# hat_v1.net
KiCad netlist of a schematic drawn in EAGLE
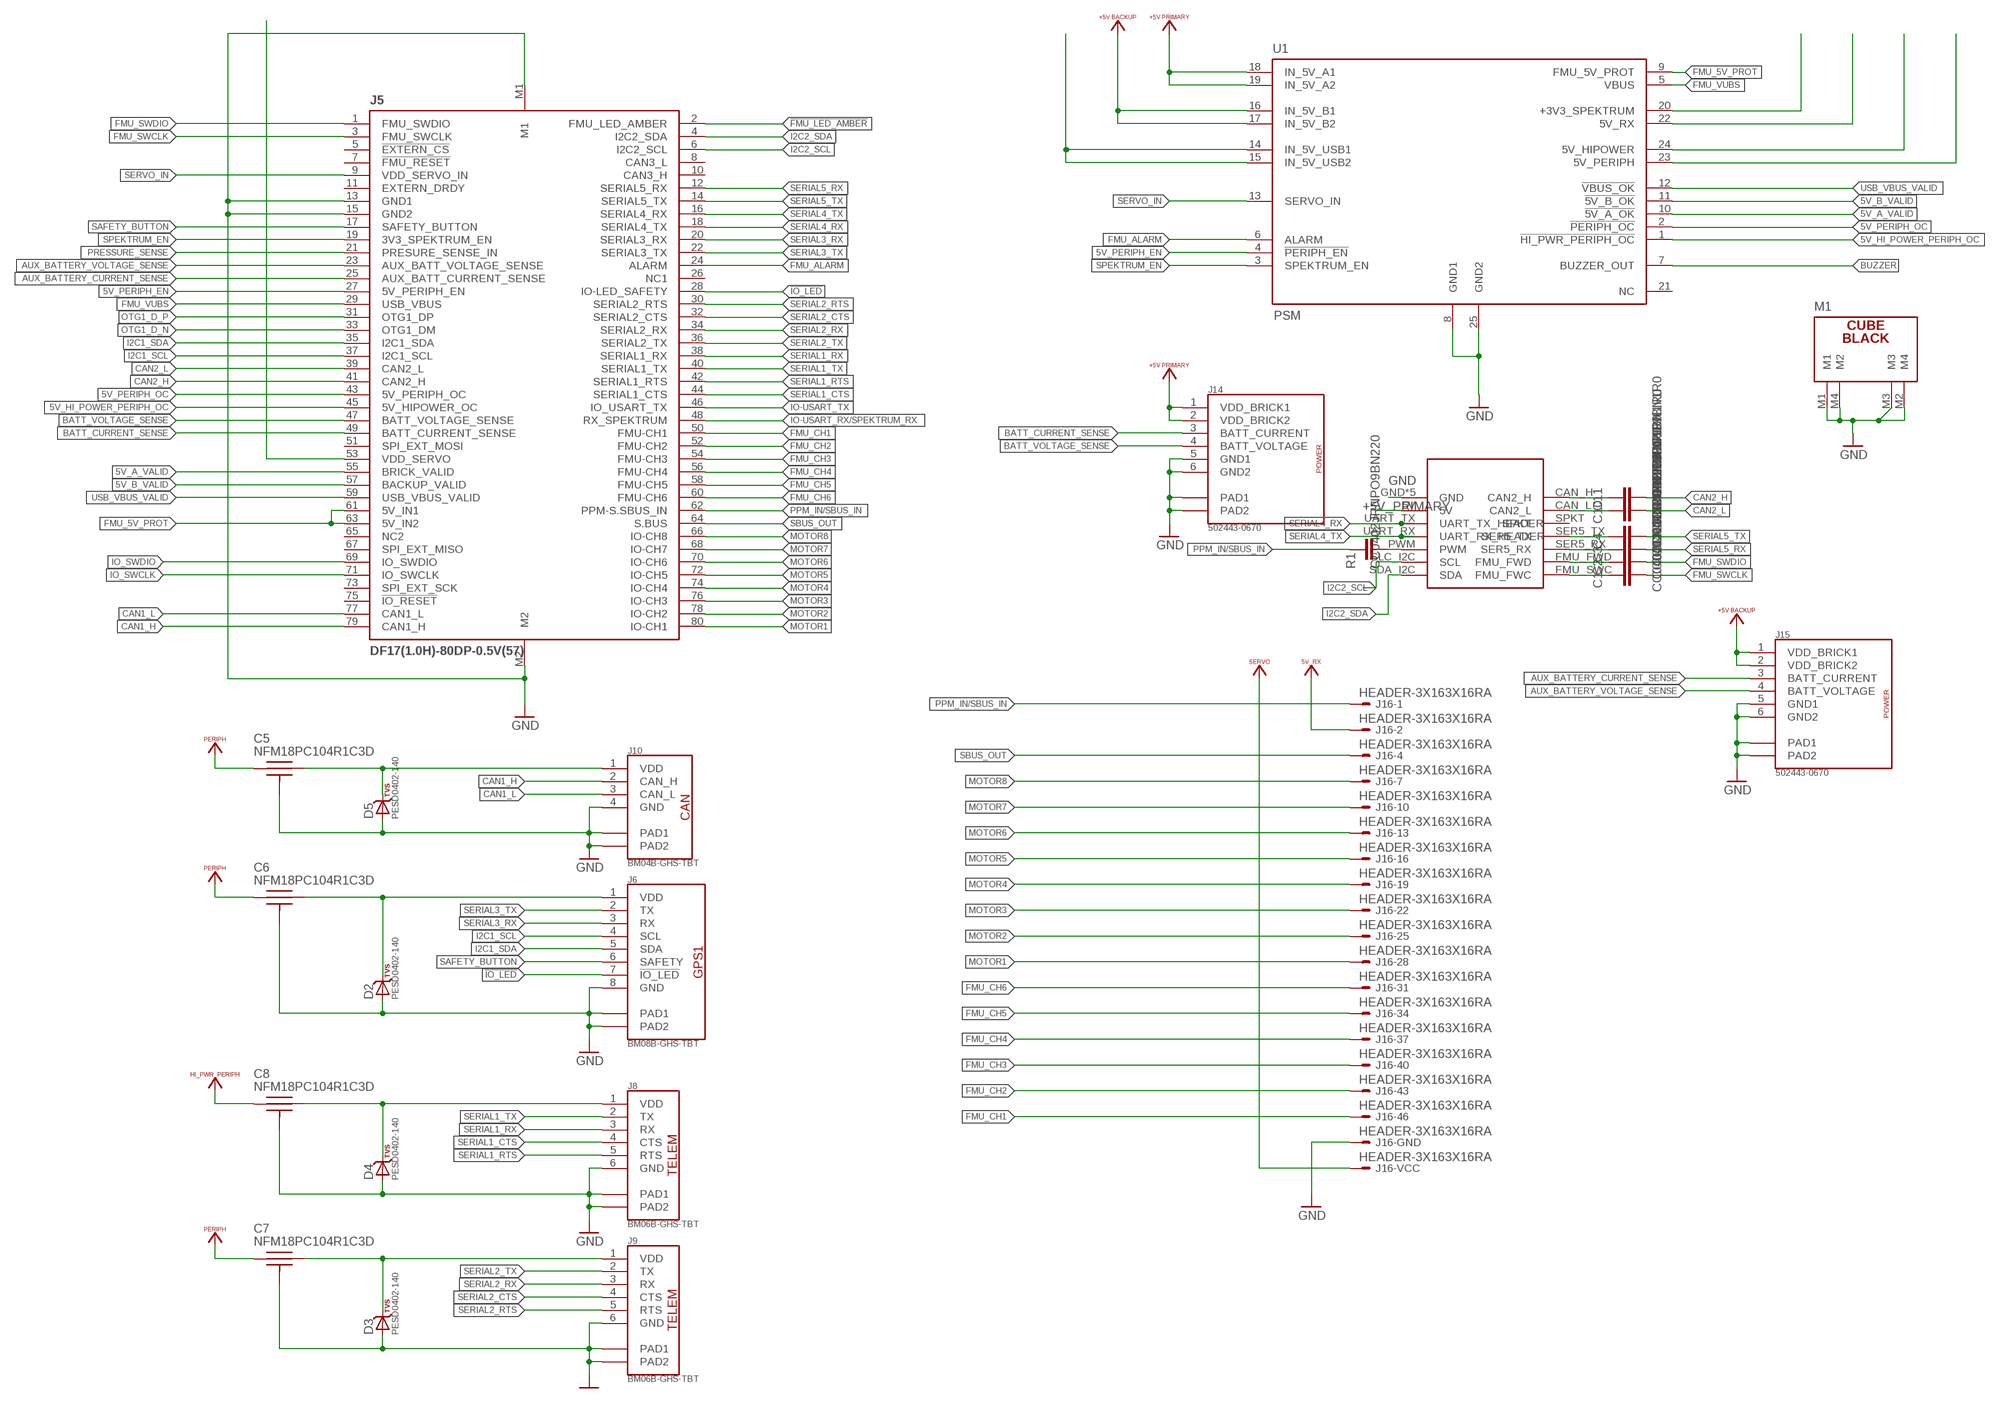
[diagram p0: schematic, sheet 1]

(export (version "E")
  (design (tool "Eeschema 10.0.6"))
  (components
    (comp (ref "C1")
      (value "CC0402CRNPO9BN1R0")
      (footprint "eagle-import:CAP_0402")
      (fields
        (field (name "DIGIKEY_PART_NUMBER") "311-2076-2-ND")
        (field (name "MANUFACTURER") "Yageo")
        (field (name "CREATED_BY") "PCBLayout.com")
      )
      (libsource (lib "eagle-import") (part "CC0402CRNPO9BN1R0"))
    )
    (comp (ref "C2")
      (value "CC0402CRNPO9BN1R0")
      (footprint "eagle-import:CAP_0402")
      (fields
        (field (name "DIGIKEY_PART_NUMBER") "311-2076-2-ND")
        (field (name "MANUFACTURER") "Yageo")
        (field (name "CREATED_BY") "PCBLayout.com")
      )
      (libsource (lib "eagle-import") (part "CC0402CRNPO9BN1R0"))
    )
    (comp (ref "C3")
      (value "CC0402CRNPO9BN1R0")
      (footprint "eagle-import:CAP_0402")
      (fields
        (field (name "DIGIKEY_PART_NUMBER") "311-2076-2-ND")
        (field (name "MANUFACTURER") "Yageo")
        (field (name "CREATED_BY") "PCBLayout.com")
      )
      (libsource (lib "eagle-import") (part "CC0402CRNPO9BN1R0"))
    )
    (comp (ref "C4")
      (value "CC0402CRNPO9BN1R0")
      (footprint "eagle-import:CAP_0402")
      (fields
        (field (name "DIGIKEY_PART_NUMBER") "311-2076-2-ND")
        (field (name "MANUFACTURER") "Yageo")
        (field (name "CREATED_BY") "PCBLayout.com")
      )
      (libsource (lib "eagle-import") (part "CC0402CRNPO9BN1R0"))
    )
    (comp (ref "C5")
      (value "NFM18PC104R1C3D")
      (footprint "eagle-import:KYOCERA-KNH16-DA")
      (libsource (lib "eagle-import") (part "NFM18PC104R1C3D"))
    )
    (comp (ref "C6")
      (value "NFM18PC104R1C3D")
      (footprint "eagle-import:KYOCERA-KNH16-DA")
      (libsource (lib "eagle-import") (part "NFM18PC104R1C3D"))
    )
    (comp (ref "C7")
      (value "NFM18PC104R1C3D")
      (footprint "eagle-import:KYOCERA-KNH16-DA")
      (libsource (lib "eagle-import") (part "NFM18PC104R1C3D"))
    )
    (comp (ref "C8")
      (value "NFM18PC104R1C3D")
      (footprint "eagle-import:KYOCERA-KNH16-DA")
      (libsource (lib "eagle-import") (part "NFM18PC104R1C3D"))
    )
    (comp (ref "C10")
      (value "CC0402CRNPO9BN1R0")
      (footprint "eagle-import:CAP_0402")
      (fields
        (field (name "DIGIKEY_PART_NUMBER") "311-2076-2-ND")
        (field (name "MANUFACTURER") "Yageo")
        (field (name "CREATED_BY") "PCBLayout.com")
      )
      (libsource (lib "eagle-import") (part "CC0402CRNPO9BN1R0"))
    )
    (comp (ref "C11")
      (value "CC0402CRNPO9BN1R0")
      (footprint "eagle-import:CAP_0402")
      (fields
        (field (name "DIGIKEY_PART_NUMBER") "311-2076-2-ND")
        (field (name "MANUFACTURER") "Yageo")
        (field (name "CREATED_BY") "PCBLayout.com")
      )
      (libsource (lib "eagle-import") (part "CC0402CRNPO9BN1R0"))
    )
    (comp (ref "D2")
      (value "PESD0402-140")
      (footprint "eagle-import:0402-TVS")
      (libsource (lib "eagle-import") (part "DIODE-TVS"))
    )
    (comp (ref "D3")
      (value "PESD0402-140")
      (footprint "eagle-import:0402-TVS")
      (libsource (lib "eagle-import") (part "DIODE-TVS"))
    )
    (comp (ref "D4")
      (value "PESD0402-140")
      (footprint "eagle-import:0402-TVS")
      (libsource (lib "eagle-import") (part "DIODE-TVS"))
    )
    (comp (ref "D5")
      (value "PESD0402-140")
      (footprint "eagle-import:0402-TVS")
      (libsource (lib "eagle-import") (part "DIODE-TVS"))
    )
    (comp (ref "J5")
      (value "DF17(1.0H)-80DP-0.5V(57)")
      (footprint "eagle-import:DF17(1.0H)-80DP-0.5V(57)")
      (libsource (lib "eagle-import") (part "DF17(1.0H)-80DP-0.5V(57)"))
    )
    (comp (ref "J6")
      (value "BM08B-GHS-TBT")
      (footprint "eagle-import:BM08B-GHS-TBT")
      (libsource (lib "eagle-import") (part "GPS1_CONNECTORBS-TBT"))
    )
    (comp (ref "J8")
      (value "BM06B-GHS-TBT")
      (footprint "eagle-import:BM06B-GHS-TBT")
      (fields (field (name "PARTNO") "BM06B-GHS-TBT(LF)(SN)"))
      (libsource (lib "eagle-import") (part "TELEM_CONNECTORBS-TBT"))
    )
    (comp (ref "J9")
      (value "BM06B-GHS-TBT")
      (footprint "eagle-import:BM06B-GHS-TBT")
      (fields (field (name "PARTNO") "BM06B-GHS-TBT(LF)(SN)"))
      (libsource (lib "eagle-import") (part "TELEM_CONNECTORBS-TBT"))
    )
    (comp (ref "J10")
      (value "BM04B-GHS-TBT")
      (footprint "eagle-import:BM04B-GHS-TBT")
      (fields (field (name "PARTNO") "BM04B-GHS-TBT(LF)(SN)"))
      (libsource (lib "eagle-import") (part "CAN_CONNECTORBS-TBT"))
    )
    (comp (ref "J14")
      (value "502443-0670")
      (footprint "eagle-import:502443-0670")
      (libsource (lib "eagle-import") (part "POWER_CONNECTOR43"))
    )
    (comp (ref "J15")
      (value "502443-0670")
      (footprint "eagle-import:502443-0670")
      (libsource (lib "eagle-import") (part "POWER_CONNECTOR43"))
    )
    (comp (ref "J16")
      (value "HEADER-3X163X16RA")
      (footprint "eagle-import:3X16RA")
      (libsource (lib "eagle-import") (part "HEADER-3X163X16RA"))
    )
    (comp (ref "M1")
      (value "CUBE_BLACK")
      (footprint "eagle-import:CUBE")
      (fields (field (name "COLOR") "BLACK"))
      (libsource (lib "eagle-import") (part "CUBE_BLACK"))
    )
    (comp (ref "R1")
      (value "CC0402JRNPO9BN220")
      (footprint "eagle-import:CAP_0402")
      (fields
        (field (name "DIGIKEY_PART_NUMBER") "311-1018-2-ND")
        (field (name "MANUFACTURER") "Yageo")
        (field (name "CREATED_BY") "PCBLayout.com")
      )
      (libsource (lib "eagle-import") (part "CC0402JRNPO9BN220"))
    )
    (comp (ref "U$1")
      (value "RPI")
      (footprint "eagle-import:RPI")
      (libsource (lib "eagle-import") (part "RPI"))
    )
    (comp (ref "U1")
      (value "PSM")
      (footprint "eagle-import:PSM")
      (libsource (lib "eagle-import") (part "PSM"))
    )
  )
  (nets
    (net (code "1") (name "+5V_BACKUP") (class "Default")
      (node (ref "J15") (pin "1") (pinfunction "VDD_BRICK1_1") (pintype "bidirectional"))
      (node (ref "J15") (pin "2") (pinfunction "VDD_BRICK2_2") (pintype "bidirectional"))
      (node (ref "U1") (pin "16") (pinfunction "IN_5V_B1_16") (pintype "bidirectional"))
      (node (ref "U1") (pin "17") (pinfunction "IN_5V_B2_17") (pintype "bidirectional"))
    )
    (net (code "2") (name "+5V_PRIMARY") (class "Default")
      (node (ref "J14") (pin "1") (pinfunction "VDD_BRICK1_1") (pintype "bidirectional"))
      (node (ref "J14") (pin "2") (pinfunction "VDD_BRICK2_2") (pintype "bidirectional"))
      (node (ref "U$1") (pin "5V") (pinfunction "5V_5V") (pintype "bidirectional"))
      (node (ref "U1") (pin "18") (pinfunction "IN_5V_A1_18") (pintype "bidirectional"))
      (node (ref "U1") (pin "19") (pinfunction "IN_5V_A2_19") (pintype "bidirectional"))
    )
    (net (code "3") (name "5V_A_VALID") (class "Default")
      (node (ref "J5") (pin "55") (pinfunction "BRICK_VALID_55") (pintype "bidirectional"))
      (node (ref "U1") (pin "10") (pinfunction "~{5V_A_OK}_10") (pintype "bidirectional"))
    )
    (net (code "4") (name "5V_B_VALID") (class "Default")
      (node (ref "J5") (pin "57") (pinfunction "BACKUP_VALID_57") (pintype "bidirectional"))
      (node (ref "U1") (pin "11") (pinfunction "~{5V_B_OK}_11") (pintype "bidirectional"))
    )
    (net (code "5") (name "5V_HI_POWER_PERIPH_OC") (class "Default")
      (node (ref "J5") (pin "45") (pinfunction "5V_HIPOWER_OC_45") (pintype "bidirectional"))
      (node (ref "U1") (pin "1") (pinfunction "~{HI_PWR_PERIPH_OC}_1") (pintype "bidirectional"))
    )
    (net (code "6") (name "5V_PERIPH_EN") (class "Default")
      (node (ref "J5") (pin "27") (pinfunction "5V_PERIPH_EN_27") (pintype "bidirectional"))
      (node (ref "U1") (pin "4") (pinfunction "~{PERIPH_EN}_4") (pintype "bidirectional"))
    )
    (net (code "7") (name "5V_PERIPH_OC") (class "Default")
      (node (ref "J5") (pin "43") (pinfunction "5V_PERIPH_OC_43") (pintype "bidirectional"))
      (node (ref "U1") (pin "2") (pinfunction "~{PERIPH_OC}_2") (pintype "bidirectional"))
    )
    (net (code "8") (name "AUX_BATTERY_CURRENT_SENSE") (class "Default")
      (node (ref "J15") (pin "3") (pinfunction "BATT_CURRENT_3") (pintype "bidirectional"))
      (node (ref "J5") (pin "25") (pinfunction "AUX_BATT_CURRENT_SENSE_25") (pintype "bidirectional"))
    )
    (net (code "9") (name "AUX_BATTERY_VOLTAGE_SENSE") (class "Default")
      (node (ref "J15") (pin "4") (pinfunction "BATT_VOLTAGE_4") (pintype "bidirectional"))
      (node (ref "J5") (pin "23") (pinfunction "AUX_BATT_VOLTAGE_SENSE_23") (pintype "bidirectional"))
    )
    (net (code "10") (name "BATT_CURRENT_SENSE") (class "Default")
      (node (ref "J14") (pin "3") (pinfunction "BATT_CURRENT_3") (pintype "bidirectional"))
      (node (ref "J5") (pin "49") (pinfunction "BATT_CURRENT_SENSE_49") (pintype "bidirectional"))
    )
    (net (code "11") (name "BATT_VOLTAGE_SENSE") (class "Default")
      (node (ref "J14") (pin "4") (pinfunction "BATT_VOLTAGE_4") (pintype "bidirectional"))
      (node (ref "J5") (pin "47") (pinfunction "BATT_VOLTAGE_SENSE_47") (pintype "bidirectional"))
    )
    (net (code "12") (name "BUZZER") (class "Default")
      (node (ref "U1") (pin "7") (pinfunction "BUZZER_OUT_7") (pintype "bidirectional"))
    )
    (net (code "13") (name "CAN1_H") (class "Default")
      (node (ref "J10") (pin "2") (pinfunction "CAN_H_2") (pintype "bidirectional"))
      (node (ref "J5") (pin "79") (pinfunction "CAN1_H_79") (pintype "bidirectional"))
    )
    (net (code "14") (name "CAN1_L") (class "Default")
      (node (ref "J10") (pin "3") (pinfunction "CAN_L_3") (pintype "bidirectional"))
      (node (ref "J5") (pin "77") (pinfunction "CAN1_L_77") (pintype "bidirectional"))
    )
    (net (code "15") (name "CAN2_H") (class "Default")
      (node (ref "C11") (pin "2") (pinfunction "2_2") (pintype "passive"))
      (node (ref "J5") (pin "41") (pinfunction "CAN2_H_41") (pintype "bidirectional"))
    )
    (net (code "16") (name "CAN2_L") (class "Default")
      (node (ref "C10") (pin "2") (pinfunction "2_2") (pintype "passive"))
      (node (ref "J5") (pin "39") (pinfunction "CAN2_L_39") (pintype "bidirectional"))
    )
    (net (code "17") (name "FMU_5V_PROT") (class "Default")
      (node (ref "J5") (pin "61") (pinfunction "5V_IN1_61") (pintype "bidirectional"))
      (node (ref "J5") (pin "63") (pinfunction "5V_IN2_63") (pintype "bidirectional"))
      (node (ref "U1") (pin "9") (pinfunction "FMU_5V_PROT_9") (pintype "bidirectional"))
    )
    (net (code "18") (name "FMU_ALARM") (class "Default")
      (node (ref "J5") (pin "24") (pinfunction "ALARM_24") (pintype "bidirectional"))
      (node (ref "U1") (pin "6") (pinfunction "ALARM_6") (pintype "bidirectional"))
    )
    (net (code "19") (name "FMU_CH1") (class "Default")
      (node (ref "J16") (pin "46") (pinfunction "S_46") (pintype "passive"))
      (node (ref "J5") (pin "50") (pinfunction "FMU-CH1_50") (pintype "bidirectional"))
    )
    (net (code "20") (name "FMU_CH2") (class "Default")
      (node (ref "J16") (pin "43") (pinfunction "S_43") (pintype "passive"))
      (node (ref "J5") (pin "52") (pinfunction "FMU-CH2_52") (pintype "bidirectional"))
    )
    (net (code "21") (name "FMU_CH3") (class "Default")
      (node (ref "J16") (pin "40") (pinfunction "S_40") (pintype "passive"))
      (node (ref "J5") (pin "54") (pinfunction "FMU-CH3_54") (pintype "bidirectional"))
    )
    (net (code "22") (name "FMU_CH4") (class "Default")
      (node (ref "J16") (pin "37") (pinfunction "S_37") (pintype "passive"))
      (node (ref "J5") (pin "56") (pinfunction "FMU-CH4_56") (pintype "bidirectional"))
    )
    (net (code "23") (name "FMU_CH5") (class "Default")
      (node (ref "J16") (pin "34") (pinfunction "S_34") (pintype "passive"))
      (node (ref "J5") (pin "58") (pinfunction "FMU-CH5_58") (pintype "bidirectional"))
    )
    (net (code "24") (name "FMU_CH6") (class "Default")
      (node (ref "J16") (pin "31") (pinfunction "S_31") (pintype "passive"))
      (node (ref "J5") (pin "60") (pinfunction "FMU-CH6_60") (pintype "bidirectional"))
    )
    (net (code "25") (name "FMU_SWCLK") (class "Default")
      (node (ref "C1") (pin "2") (pinfunction "2_2") (pintype "passive"))
      (node (ref "J5") (pin "3") (pinfunction "FMU_SWCLK_3") (pintype "bidirectional"))
    )
    (net (code "26") (name "FMU_SWDIO") (class "Default")
      (node (ref "C2") (pin "2") (pinfunction "2_2") (pintype "passive"))
      (node (ref "J5") (pin "1") (pinfunction "FMU_SWDIO_1") (pintype "bidirectional"))
    )
    (net (code "27") (name "FMU_VUBS") (class "Default")
      (node (ref "J5") (pin "29") (pinfunction "USB_VBUS_29") (pintype "bidirectional"))
      (node (ref "U1") (pin "5") (pinfunction "VBUS_5") (pintype "bidirectional"))
    )
    (net (code "28") (name "GND") (class "Default")
      (node (ref "C5") (pin "P$3") (pinfunction "P$3_P$3") (pintype "bidirectional"))
      (node (ref "C5") (pin "P$4") (pinfunction "P$3_P$4") (pintype "bidirectional"))
      (node (ref "C5") (pin "P$5") (pinfunction "P$3_P$5") (pintype "bidirectional"))
      (node (ref "C6") (pin "P$3") (pinfunction "P$3_P$3") (pintype "bidirectional"))
      (node (ref "C6") (pin "P$4") (pinfunction "P$3_P$4") (pintype "bidirectional"))
      (node (ref "C6") (pin "P$5") (pinfunction "P$3_P$5") (pintype "bidirectional"))
      (node (ref "C7") (pin "P$3") (pinfunction "P$3_P$3") (pintype "bidirectional"))
      (node (ref "C7") (pin "P$4") (pinfunction "P$3_P$4") (pintype "bidirectional"))
      (node (ref "C7") (pin "P$5") (pinfunction "P$3_P$5") (pintype "bidirectional"))
      (node (ref "C8") (pin "P$3") (pinfunction "P$3_P$3") (pintype "bidirectional"))
      (node (ref "C8") (pin "P$4") (pinfunction "P$3_P$4") (pintype "bidirectional"))
      (node (ref "C8") (pin "P$5") (pinfunction "P$3_P$5") (pintype "bidirectional"))
      (node (ref "D2") (pin "A") (pinfunction "A_A") (pintype "passive"))
      (node (ref "D3") (pin "A") (pinfunction "A_A") (pintype "passive"))
      (node (ref "D4") (pin "A") (pinfunction "A_A") (pintype "passive"))
      (node (ref "D5") (pin "A") (pinfunction "A_A") (pintype "passive"))
      (node (ref "J10") (pin "4") (pinfunction "GND_4") (pintype "bidirectional"))
      (node (ref "J10") (pin "PAD1") (pinfunction "PAD1_PAD1") (pintype "bidirectional"))
      (node (ref "J10") (pin "PAD2") (pinfunction "PAD2_PAD2") (pintype "bidirectional"))
      (node (ref "J14") (pin "5") (pinfunction "GND1_5") (pintype "bidirectional"))
      (node (ref "J14") (pin "6") (pinfunction "GND2_6") (pintype "bidirectional"))
      (node (ref "J14") (pin "PAD1") (pinfunction "PAD1_PAD1") (pintype "bidirectional"))
      (node (ref "J14") (pin "PAD2") (pinfunction "PAD2_PAD2") (pintype "bidirectional"))
      (node (ref "J15") (pin "5") (pinfunction "GND1_5") (pintype "bidirectional"))
      (node (ref "J15") (pin "6") (pinfunction "GND2_6") (pintype "bidirectional"))
      (node (ref "J15") (pin "PAD1") (pinfunction "PAD1_PAD1") (pintype "bidirectional"))
      (node (ref "J15") (pin "PAD2") (pinfunction "PAD2_PAD2") (pintype "bidirectional"))
      (node (ref "J16") (pin "12") (pinfunction "S_12") (pintype "passive"))
      (node (ref "J16") (pin "15") (pinfunction "S_15") (pintype "passive"))
      (node (ref "J16") (pin "18") (pinfunction "S_18") (pintype "passive"))
      (node (ref "J16") (pin "21") (pinfunction "S_21") (pintype "passive"))
      (node (ref "J16") (pin "24") (pinfunction "S_24") (pintype "passive"))
      (node (ref "J16") (pin "27") (pinfunction "S_27") (pintype "passive"))
      (node (ref "J16") (pin "3") (pinfunction "S_3") (pintype "passive"))
      (node (ref "J16") (pin "30") (pinfunction "S_30") (pintype "passive"))
      (node (ref "J16") (pin "33") (pinfunction "S_33") (pintype "passive"))
      (node (ref "J16") (pin "36") (pinfunction "S_36") (pintype "passive"))
      (node (ref "J16") (pin "39") (pinfunction "S_39") (pintype "passive"))
      (node (ref "J16") (pin "42") (pinfunction "S_42") (pintype "passive"))
      (node (ref "J16") (pin "45") (pinfunction "S_45") (pintype "passive"))
      (node (ref "J16") (pin "48") (pinfunction "S_48") (pintype "passive"))
      (node (ref "J16") (pin "6") (pinfunction "S_6") (pintype "passive"))
      (node (ref "J16") (pin "9") (pinfunction "S_9") (pintype "passive"))
      (node (ref "J5") (pin "13") (pinfunction "GND1_13") (pintype "bidirectional"))
      (node (ref "J5") (pin "15") (pinfunction "GND2_15") (pintype "bidirectional"))
      (node (ref "J5") (pin "M1") (pinfunction "M1_M1") (pintype "bidirectional"))
      (node (ref "J5") (pin "M2") (pinfunction "M2_M2") (pintype "bidirectional"))
      (node (ref "J6") (pin "8") (pinfunction "GND_8") (pintype "bidirectional"))
      (node (ref "J6") (pin "PAD1") (pinfunction "PAD1_PAD1") (pintype "bidirectional"))
      (node (ref "J6") (pin "PAD2") (pinfunction "PAD2_PAD2") (pintype "bidirectional"))
      (node (ref "J8") (pin "6") (pinfunction "GND_6") (pintype "bidirectional"))
      (node (ref "J8") (pin "PAD1") (pinfunction "PAD1_PAD1") (pintype "bidirectional"))
      (node (ref "J8") (pin "PAD2") (pinfunction "PAD2_PAD2") (pintype "bidirectional"))
      (node (ref "J9") (pin "6") (pinfunction "GND_6") (pintype "bidirectional"))
      (node (ref "J9") (pin "PAD1") (pinfunction "PAD1_PAD1") (pintype "bidirectional"))
      (node (ref "J9") (pin "PAD2") (pinfunction "PAD2_PAD2") (pintype "bidirectional"))
      (node (ref "M1") (pin "M1") (pinfunction "M1_M1") (pintype "bidirectional"))
      (node (ref "M1") (pin "M2") (pinfunction "M4_M2") (pintype "bidirectional"))
      (node (ref "M1") (pin "M3") (pinfunction "M3_M3") (pintype "bidirectional"))
      (node (ref "M1") (pin "M4") (pinfunction "M2_M4") (pintype "bidirectional"))
      (node (ref "U$1") (pin "GND") (pinfunction "GND_GND") (pintype "bidirectional"))
      (node (ref "U$1") (pin "GND1") (pinfunction "GND_GND1") (pintype "bidirectional"))
      (node (ref "U$1") (pin "GND2") (pinfunction "GND_GND2") (pintype "bidirectional"))
      (node (ref "U$1") (pin "GND3") (pinfunction "GND_GND3") (pintype "bidirectional"))
      (node (ref "U$1") (pin "GND4") (pinfunction "GND_GND4") (pintype "bidirectional"))
      (node (ref "U1") (pin "25") (pinfunction "GND2_25") (pintype "bidirectional"))
      (node (ref "U1") (pin "8") (pinfunction "GND1_8") (pintype "bidirectional"))
    )
    (net (code "29") (name "I2C1_SCL") (class "Default")
      (node (ref "J5") (pin "37") (pinfunction "I2C1_SCL_37") (pintype "bidirectional"))
      (node (ref "J6") (pin "4") (pinfunction "SCL_4") (pintype "bidirectional"))
    )
    (net (code "30") (name "I2C1_SDA") (class "Default")
      (node (ref "J5") (pin "35") (pinfunction "I2C1_SDA_35") (pintype "bidirectional"))
      (node (ref "J6") (pin "5") (pinfunction "SDA_5") (pintype "bidirectional"))
    )
    (net (code "31") (name "I2C2_SCL") (class "Default")
      (node (ref "J5") (pin "6") (pinfunction "I2C2_SCL_6") (pintype "bidirectional"))
      (node (ref "U$1") (pin "SLC_I2C") (pinfunction "SCL_SLC_I2C") (pintype "bidirectional"))
    )
    (net (code "32") (name "I2C2_SDA") (class "Default")
      (node (ref "J5") (pin "4") (pinfunction "I2C2_SDA_4") (pintype "bidirectional"))
      (node (ref "U$1") (pin "SDA_I2C") (pinfunction "SDA_SDA_I2C") (pintype "bidirectional"))
    )
    (net (code "33") (name "IO-USART_RX{slash}SPEKTRUM_RX") (class "Default")
      (node (ref "J5") (pin "48") (pinfunction "RX_SPEKTRUM_48") (pintype "bidirectional"))
    )
    (net (code "34") (name "IO-USART_TX") (class "Default")
      (node (ref "J5") (pin "46") (pinfunction "IO_USART_TX_46") (pintype "bidirectional"))
    )
    (net (code "35") (name "IO_SWCLK") (class "Default")
      (node (ref "J5") (pin "71") (pinfunction "IO_SWCLK_71") (pintype "bidirectional"))
    )
    (net (code "36") (name "IO_SWDIO") (class "Default")
      (node (ref "J5") (pin "69") (pinfunction "IO_SWDIO_69") (pintype "bidirectional"))
    )
    (net (code "37") (name "MOTOR1") (class "Default")
      (node (ref "J16") (pin "28") (pinfunction "S_28") (pintype "passive"))
      (node (ref "J5") (pin "80") (pinfunction "IO-CH1_80") (pintype "bidirectional"))
    )
    (net (code "38") (name "MOTOR2") (class "Default")
      (node (ref "J16") (pin "25") (pinfunction "S_25") (pintype "passive"))
      (node (ref "J5") (pin "78") (pinfunction "IO-CH2_78") (pintype "bidirectional"))
    )
    (net (code "39") (name "MOTOR3") (class "Default")
      (node (ref "J16") (pin "22") (pinfunction "S_22") (pintype "passive"))
      (node (ref "J5") (pin "76") (pinfunction "IO-CH3_76") (pintype "bidirectional"))
    )
    (net (code "40") (name "MOTOR4") (class "Default")
      (node (ref "J16") (pin "19") (pinfunction "S_19") (pintype "passive"))
      (node (ref "J5") (pin "74") (pinfunction "IO-CH4_74") (pintype "bidirectional"))
    )
    (net (code "41") (name "MOTOR5") (class "Default")
      (node (ref "J16") (pin "16") (pinfunction "S_16") (pintype "passive"))
      (node (ref "J5") (pin "72") (pinfunction "IO-CH5_72") (pintype "bidirectional"))
    )
    (net (code "42") (name "MOTOR6") (class "Default")
      (node (ref "J16") (pin "13") (pinfunction "S_13") (pintype "passive"))
      (node (ref "J5") (pin "70") (pinfunction "IO-CH6_70") (pintype "bidirectional"))
    )
    (net (code "43") (name "MOTOR7") (class "Default")
      (node (ref "J16") (pin "10") (pinfunction "S_10") (pintype "passive"))
      (node (ref "J5") (pin "68") (pinfunction "IO-CH7_68") (pintype "bidirectional"))
    )
    (net (code "44") (name "MOTOR8") (class "Default")
      (node (ref "J16") (pin "7") (pinfunction "S_7") (pintype "passive"))
      (node (ref "J5") (pin "66") (pinfunction "IO-CH8_66") (pintype "bidirectional"))
    )
    (net (code "45") (name "Net-(C2-Pad1)") (class "Default")
      (node (ref "C2") (pin "1") (pinfunction "1_1") (pintype "passive"))
      (node (ref "U$1") (pin "FMU_FWD") (pinfunction "FMU_FWD_FMU_FWD") (pintype "bidirectional"))
    )
    (net (code "46") (name "Net-(C3-Pad1)") (class "Default")
      (node (ref "C3") (pin "1") (pinfunction "1_1") (pintype "passive"))
      (node (ref "U$1") (pin "SER5_RX") (pinfunction "SER5_RX_SER5_RX") (pintype "bidirectional"))
    )
    (net (code "47") (name "Net-(C4-Pad1)") (class "Default")
      (node (ref "C4") (pin "1") (pinfunction "1_1") (pintype "passive"))
      (node (ref "U$1") (pin "SER5_TX") (pinfunction "SER5_TX_SER5_TX") (pintype "bidirectional"))
    )
    (net (code "48") (name "Net-(J6-VDD)") (class "Default")
      (node (ref "C6") (pin "P$2") (pinfunction "P$2_P$2") (pintype "bidirectional"))
      (node (ref "D2") (pin "C") (pinfunction "C_C") (pintype "passive"))
      (node (ref "J6") (pin "1") (pinfunction "VDD_1") (pintype "bidirectional"))
    )
    (net (code "49") (name "Net-(J8-VDD)") (class "Default")
      (node (ref "C8") (pin "P$2") (pinfunction "P$2_P$2") (pintype "bidirectional"))
      (node (ref "D4") (pin "C") (pinfunction "C_C") (pintype "passive"))
      (node (ref "J8") (pin "1") (pinfunction "VDD_1") (pintype "bidirectional"))
    )
    (net (code "50") (name "Net-(J9-VDD)") (class "Default")
      (node (ref "C7") (pin "P$2") (pinfunction "P$2_P$2") (pintype "bidirectional"))
      (node (ref "D3") (pin "C") (pinfunction "C_C") (pintype "passive"))
      (node (ref "J9") (pin "1") (pinfunction "VDD_1") (pintype "bidirectional"))
    )
    (net (code "51") (name "Net-(J10-VDD)") (class "Default")
      (node (ref "C5") (pin "P$2") (pinfunction "P$2_P$2") (pintype "bidirectional"))
      (node (ref "D5") (pin "C") (pinfunction "C_C") (pintype "passive"))
      (node (ref "J10") (pin "1") (pinfunction "VDD_1") (pintype "bidirectional"))
    )
    (net (code "52") (name "Net-(R1-Pad2)") (class "Default")
      (node (ref "R1") (pin "2") (pinfunction "2_2") (pintype "passive"))
      (node (ref "U$1") (pin "PWM") (pinfunction "PWM_PWM") (pintype "bidirectional"))
    )
    (net (code "53") (name "Net-(U$1-CAN2_H)") (class "Default")
      (node (ref "C11") (pin "1") (pinfunction "1_1") (pintype "passive"))
      (node (ref "U$1") (pin "CAN_H") (pinfunction "CAN2_H_CAN_H") (pintype "bidirectional"))
    )
    (net (code "54") (name "Net-(U$1-CAN2_L)") (class "Default")
      (node (ref "C10") (pin "1") (pinfunction "1_1") (pintype "passive"))
      (node (ref "U$1") (pin "CAN_L") (pinfunction "CAN2_L_CAN_L") (pintype "bidirectional"))
    )
    (net (code "55") (name "Net-(U$1-FMU_FWC)") (class "Default")
      (node (ref "C1") (pin "1") (pinfunction "1_1") (pintype "passive"))
      (node (ref "U$1") (pin "FMU_SWC") (pinfunction "FMU_FWC_FMU_SWC") (pintype "bidirectional"))
    )
    (net (code "56") (name "Net-(U1-IN_5V_USB1)") (class "Default")
      (node (ref "U1") (pin "14") (pinfunction "IN_5V_USB1_14") (pintype "bidirectional"))
      (node (ref "U1") (pin "15") (pinfunction "IN_5V_USB2_15") (pintype "bidirectional"))
    )
    (net (code "57") (name "OTG1_D_N") (class "Default")
      (node (ref "J5") (pin "33") (pinfunction "OTG1_DM_33") (pintype "bidirectional"))
    )
    (net (code "58") (name "OTG1_D_P") (class "Default")
      (node (ref "J5") (pin "31") (pinfunction "OTG1_DP_31") (pintype "bidirectional"))
    )
    (net (code "59") (name "PPM_IN{slash}SBUS_IN") (class "Default")
      (node (ref "J16") (pin "1") (pinfunction "S_1") (pintype "passive"))
      (node (ref "J5") (pin "62") (pinfunction "PPM-S.SBUS_IN_62") (pintype "bidirectional"))
      (node (ref "R1") (pin "1") (pinfunction "1_1") (pintype "passive"))
    )
    (net (code "60") (name "PRESSURE_SENSE") (class "Default")
      (node (ref "J5") (pin "21") (pinfunction "PRESURE_SENSE_IN_21") (pintype "bidirectional"))
    )
    (net (code "61") (name "SAFETY_BUTTON") (class "Default")
      (node (ref "J5") (pin "17") (pinfunction "SAFETY_BUTTON_17") (pintype "bidirectional"))
      (node (ref "J6") (pin "6") (pinfunction "SAFETY_6") (pintype "bidirectional"))
    )
    (net (code "62") (name "SBUS_OUT") (class "Default")
      (node (ref "J16") (pin "4") (pinfunction "S_4") (pintype "passive"))
      (node (ref "J5") (pin "64") (pinfunction "S.BUS_64") (pintype "bidirectional"))
    )
    (net (code "63") (name "SERIAL1_CTS") (class "Default")
      (node (ref "J5") (pin "44") (pinfunction "SERIAL1_CTS_44") (pintype "bidirectional"))
      (node (ref "J8") (pin "4") (pinfunction "CTS_4") (pintype "bidirectional"))
    )
    (net (code "64") (name "SERIAL1_RTS") (class "Default")
      (node (ref "J5") (pin "42") (pinfunction "SERIAL1_RTS_42") (pintype "bidirectional"))
      (node (ref "J8") (pin "5") (pinfunction "RTS_5") (pintype "bidirectional"))
    )
    (net (code "65") (name "SERIAL1_RX") (class "Default")
      (node (ref "J5") (pin "38") (pinfunction "SERIAL1_RX_38") (pintype "bidirectional"))
      (node (ref "J8") (pin "3") (pinfunction "RX_3") (pintype "bidirectional"))
    )
    (net (code "66") (name "SERIAL1_TX") (class "Default")
      (node (ref "J5") (pin "40") (pinfunction "SERIAL1_TX_40") (pintype "bidirectional"))
      (node (ref "J8") (pin "2") (pinfunction "TX_2") (pintype "bidirectional"))
    )
    (net (code "67") (name "SERIAL2_CTS") (class "Default")
      (node (ref "J5") (pin "32") (pinfunction "SERIAL2_CTS_32") (pintype "bidirectional"))
      (node (ref "J9") (pin "4") (pinfunction "CTS_4") (pintype "bidirectional"))
    )
    (net (code "68") (name "SERIAL2_RTS") (class "Default")
      (node (ref "J5") (pin "30") (pinfunction "SERIAL2_RTS_30") (pintype "bidirectional"))
      (node (ref "J9") (pin "5") (pinfunction "RTS_5") (pintype "bidirectional"))
    )
    (net (code "69") (name "SERIAL2_RX") (class "Default")
      (node (ref "J5") (pin "34") (pinfunction "SERIAL2_RX_34") (pintype "bidirectional"))
      (node (ref "J9") (pin "3") (pinfunction "RX_3") (pintype "bidirectional"))
    )
    (net (code "70") (name "SERIAL2_TX") (class "Default")
      (node (ref "J5") (pin "36") (pinfunction "SERIAL2_TX_36") (pintype "bidirectional"))
      (node (ref "J9") (pin "2") (pinfunction "TX_2") (pintype "bidirectional"))
    )
    (net (code "71") (name "SERIAL3_RX") (class "Default")
      (node (ref "J5") (pin "20") (pinfunction "SERIAL3_RX_20") (pintype "bidirectional"))
      (node (ref "J6") (pin "3") (pinfunction "RX_3") (pintype "bidirectional"))
    )
    (net (code "72") (name "SERIAL3_TX") (class "Default")
      (node (ref "J5") (pin "22") (pinfunction "SERIAL3_TX_22") (pintype "bidirectional"))
      (node (ref "J6") (pin "2") (pinfunction "TX_2") (pintype "bidirectional"))
    )
    (net (code "73") (name "SERIAL4_RX") (class "Default")
      (node (ref "J5") (pin "18") (pinfunction "SERIAL4_TX_18") (pintype "bidirectional"))
      (node (ref "U$1") (pin "UART_RX") (pinfunction "UART_RX_HEADER_UART_RX") (pintype "bidirectional"))
    )
    (net (code "74") (name "SERIAL4_TX") (class "Default")
      (node (ref "J5") (pin "16") (pinfunction "SERIAL4_RX_16") (pintype "bidirectional"))
      (node (ref "U$1") (pin "UART_TX") (pinfunction "UART_TX_HEADER_UART_TX") (pintype "bidirectional"))
    )
    (net (code "75") (name "SERIAL5_RX") (class "Default")
      (node (ref "C3") (pin "2") (pinfunction "2_2") (pintype "passive"))
      (node (ref "J5") (pin "12") (pinfunction "SERIAL5_RX_12") (pintype "bidirectional"))
    )
    (net (code "76") (name "SERIAL5_TX") (class "Default")
      (node (ref "C4") (pin "2") (pinfunction "2_2") (pintype "passive"))
      (node (ref "J5") (pin "14") (pinfunction "SERIAL5_TX_14") (pintype "bidirectional"))
    )
    (net (code "77") (name "SERVO_IN") (class "Default")
      (node (ref "J5") (pin "9") (pinfunction "VDD_SERVO_IN_9") (pintype "bidirectional"))
      (node (ref "U1") (pin "13") (pinfunction "SERVO_IN_13") (pintype "bidirectional"))
    )
    (net (code "78") (name "SPEKTRUM_EN") (class "Default")
      (node (ref "J5") (pin "19") (pinfunction "3V3_SPEKTRUM_EN_19") (pintype "bidirectional"))
      (node (ref "U1") (pin "3") (pinfunction "SPEKTRUM_EN_3") (pintype "bidirectional"))
    )
    (net (code "79") (name "USB_VBUS_VALID") (class "Default")
      (node (ref "J5") (pin "59") (pinfunction "USB_VBUS_VALID_59") (pintype "bidirectional"))
      (node (ref "U1") (pin "12") (pinfunction "~{VBUS_OK}_12") (pintype "bidirectional"))
    )
    (net (code "80") (name "VCCIO") (class "Default")
      (node (ref "J16") (pin "2") (pinfunction "S_2") (pintype "passive"))
      (node (ref "U1") (pin "22") (pinfunction "5V_RX_22") (pintype "bidirectional"))
    )
    (net (code "81") (name "VDD_HI_PWR_PERIPH") (class "Default")
      (node (ref "C8") (pin "P$1") (pinfunction "P$1_P$1") (pintype "bidirectional"))
      (node (ref "U1") (pin "24") (pinfunction "5V_HIPOWER_24") (pintype "bidirectional"))
    )
    (net (code "82") (name "VDD_PERIPH") (class "Default")
      (node (ref "C5") (pin "P$1") (pinfunction "P$1_P$1") (pintype "bidirectional"))
      (node (ref "C6") (pin "P$1") (pinfunction "P$1_P$1") (pintype "bidirectional"))
      (node (ref "C7") (pin "P$1") (pinfunction "P$1_P$1") (pintype "bidirectional"))
      (node (ref "U1") (pin "23") (pinfunction "5V_PERIPH_23") (pintype "bidirectional"))
    )
    (net (code "83") (name "VSERVO") (class "Default")
      (node (ref "J16") (pin "11") (pinfunction "S_11") (pintype "passive"))
      (node (ref "J16") (pin "14") (pinfunction "S_14") (pintype "passive"))
      (node (ref "J16") (pin "17") (pinfunction "S_17") (pintype "passive"))
      (node (ref "J16") (pin "20") (pinfunction "S_20") (pintype "passive"))
      (node (ref "J16") (pin "23") (pinfunction "S_23") (pintype "passive"))
      (node (ref "J16") (pin "26") (pinfunction "S_26") (pintype "passive"))
      (node (ref "J16") (pin "29") (pinfunction "S_29") (pintype "passive"))
      (node (ref "J16") (pin "32") (pinfunction "S_32") (pintype "passive"))
      (node (ref "J16") (pin "35") (pinfunction "S_35") (pintype "passive"))
      (node (ref "J16") (pin "38") (pinfunction "S_38") (pintype "passive"))
      (node (ref "J16") (pin "41") (pinfunction "S_41") (pintype "passive"))
      (node (ref "J16") (pin "44") (pinfunction "S_44") (pintype "passive"))
      (node (ref "J16") (pin "47") (pinfunction "S_47") (pintype "passive"))
      (node (ref "J16") (pin "5") (pinfunction "S_5") (pintype "passive"))
      (node (ref "J16") (pin "8") (pinfunction "S_8") (pintype "passive"))
      (node (ref "J5") (pin "53") (pinfunction "VDD_SERVO_53") (pintype "bidirectional"))
    )
    (net (code "84") (name "unconnected-(J5-CAN3_H-Pad10)") (class "Default")
      (node (ref "J5") (pin "10") (pinfunction "CAN3_H_10") (pintype "bidirectional"))
    )
    (net (code "85") (name "unconnected-(J5-CAN3_L-Pad8)") (class "Default")
      (node (ref "J5") (pin "8") (pinfunction "CAN3_L_8") (pintype "bidirectional"))
    )
    (net (code "86") (name "unconnected-(J5-EXTERN_DRDY-Pad11)") (class "Default")
      (node (ref "J5") (pin "11") (pinfunction "EXTERN_DRDY_11") (pintype "bidirectional"))
    )
    (net (code "87") (name "unconnected-(J5-NC1-Pad26)") (class "Default")
      (node (ref "J5") (pin "26") (pinfunction "NC1_26") (pintype "bidirectional"))
    )
    (net (code "88") (name "unconnected-(J5-NC2-Pad65)") (class "Default")
      (node (ref "J5") (pin "65") (pinfunction "NC2_65") (pintype "bidirectional"))
    )
    (net (code "89") (name "unconnected-(J5-SPI_EXT_MISO-Pad67)") (class "Default")
      (node (ref "J5") (pin "67") (pinfunction "SPI_EXT_MISO_67") (pintype "bidirectional"))
    )
    (net (code "90") (name "unconnected-(J5-SPI_EXT_MOSI-Pad51)") (class "Default")
      (node (ref "J5") (pin "51") (pinfunction "SPI_EXT_MOSI_51") (pintype "bidirectional"))
    )
    (net (code "91") (name "unconnected-(J5-SPI_EXT_SCK-Pad73)") (class "Default")
      (node (ref "J5") (pin "73") (pinfunction "SPI_EXT_SCK_73") (pintype "bidirectional"))
    )
    (net (code "92") (name "unconnected-(J5-~{EXTERN_CS}-Pad5)") (class "Default")
      (node (ref "J5") (pin "5") (pinfunction "~{EXTERN_CS}_5") (pintype "bidirectional"))
    )
    (net (code "93") (name "unconnected-(J5-~{FMU_RESET}-Pad7)") (class "Default")
      (node (ref "J5") (pin "7") (pinfunction "~{FMU_RESET}_7") (pintype "bidirectional"))
    )
    (net (code "94") (name "unconnected-(J5-~{IO_RESET}-Pad75)") (class "Default")
      (node (ref "J5") (pin "75") (pinfunction "~{IO_RESET}_75") (pintype "bidirectional"))
    )
    (net (code "95") (name "unconnected-(U$1-PadSPKT)") (class "Default")
      (node (ref "U$1") (pin "SPKT") (pinfunction "SPKT_SPKT") (pintype "bidirectional"))
    )
    (net (code "96") (name "unconnected-(U1-+3V3_SPEKTRUM-Pad20)") (class "Default")
      (node (ref "U1") (pin "20") (pinfunction "+3V3_SPEKTRUM_20") (pintype "bidirectional"))
    )
    (net (code "97") (name "unconnected-(U1-NC-Pad21)") (class "Default")
      (node (ref "U1") (pin "21") (pinfunction "NC_21") (pintype "bidirectional"))
    )
    (net (code "98") (name "~{FMU_LED_AMBER}") (class "Default")
      (node (ref "J5") (pin "2") (pinfunction "FMU_LED_AMBER_2") (pintype "bidirectional"))
    )
    (net (code "99") (name "~{IO_LED}") (class "Default")
      (node (ref "J5") (pin "28") (pinfunction "IO-LED_SAFETY_28") (pintype "bidirectional"))
      (node (ref "J6") (pin "7") (pinfunction "~{IO_LED}_7") (pintype "bidirectional"))
    )
  )
)
